# haasoscope_pro_input_board.net
KiCad netlist of a schematic drawn in EAGLE
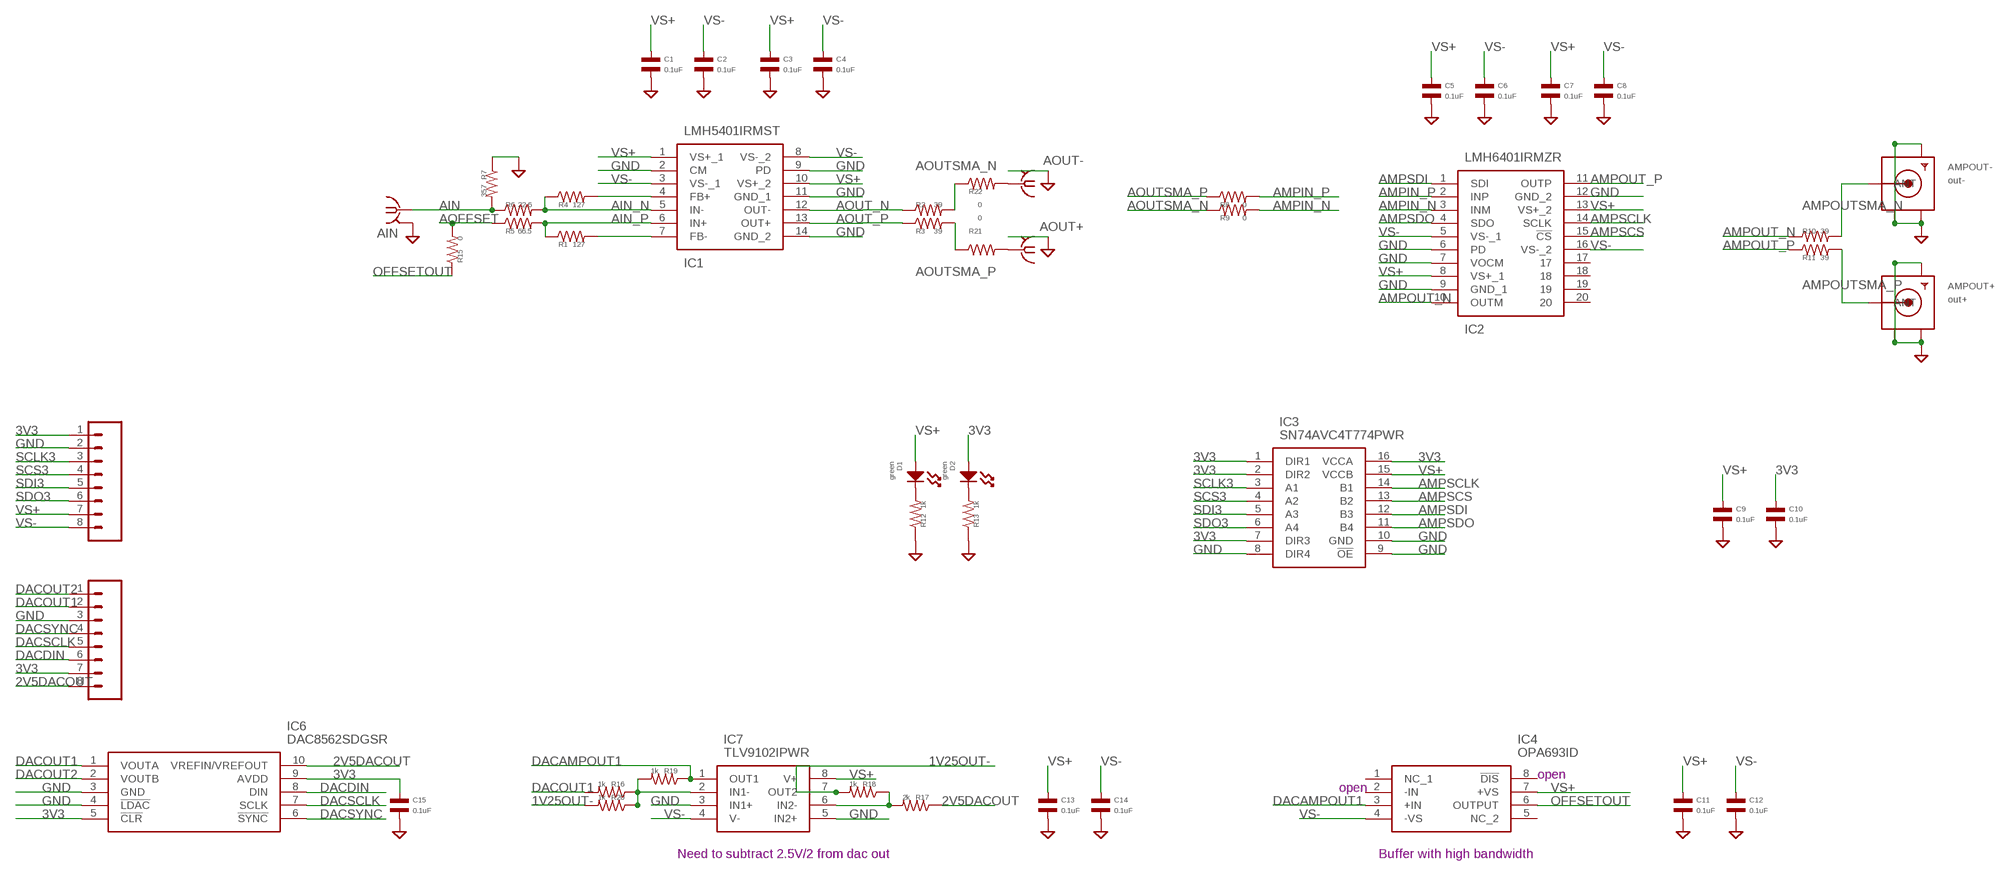
[diagram p0: schematic, sheet 1]

(export (version "E")
  (design (tool "Eeschema 10.0.6"))
  (components
    (comp (ref "AIN")
      (value "BU-SMB-V")
      (footprint "eagle-import:BU-SMB-V")
      (libsource (lib "eagle-import") (part "BU-SMB-V"))
    )
    (comp (ref "AMPOUT+")
      (value "out+")
      (footprint "eagle-import:SMA_EDGELAUNCH")
      (libsource (lib "eagle-import") (part "SMACONNECTOR_EDGE"))
    )
    (comp (ref "AMPOUT-")
      (value "out-")
      (footprint "eagle-import:SMA_EDGELAUNCH")
      (libsource (lib "eagle-import") (part "SMACONNECTOR_EDGE"))
    )
    (comp (ref "AOUT+")
      (value "BU-SMB-V")
      (footprint "eagle-import:BU-SMB-V")
      (libsource (lib "eagle-import") (part "BU-SMB-V"))
    )
    (comp (ref "AOUT-")
      (value "BU-SMB-V")
      (footprint "eagle-import:BU-SMB-V")
      (libsource (lib "eagle-import") (part "BU-SMB-V"))
    )
    (comp (ref "C1")
      (value "0.1uF")
      (footprint "eagle-import:C0402")
      (libsource (lib "eagle-import") (part "CAPACITOR_NP_0402"))
    )
    (comp (ref "C2")
      (value "0.1uF")
      (footprint "eagle-import:C0402")
      (libsource (lib "eagle-import") (part "CAPACITOR_NP_0402"))
    )
    (comp (ref "C3")
      (value "0.1uF")
      (footprint "eagle-import:C0402")
      (libsource (lib "eagle-import") (part "CAPACITOR_NP_0402"))
    )
    (comp (ref "C4")
      (value "0.1uF")
      (footprint "eagle-import:C0402")
      (libsource (lib "eagle-import") (part "CAPACITOR_NP_0402"))
    )
    (comp (ref "C5")
      (value "0.1uF")
      (footprint "eagle-import:C0402")
      (libsource (lib "eagle-import") (part "CAPACITOR_NP_0402"))
    )
    (comp (ref "C6")
      (value "0.1uF")
      (footprint "eagle-import:C0402")
      (libsource (lib "eagle-import") (part "CAPACITOR_NP_0402"))
    )
    (comp (ref "C7")
      (value "0.1uF")
      (footprint "eagle-import:C0402")
      (libsource (lib "eagle-import") (part "CAPACITOR_NP_0402"))
    )
    (comp (ref "C8")
      (value "0.1uF")
      (footprint "eagle-import:C0402")
      (libsource (lib "eagle-import") (part "CAPACITOR_NP_0402"))
    )
    (comp (ref "C9")
      (value "0.1uF")
      (footprint "eagle-import:C0402")
      (libsource (lib "eagle-import") (part "CAPACITOR_NP_0402"))
    )
    (comp (ref "C10")
      (value "0.1uF")
      (footprint "eagle-import:C0402")
      (libsource (lib "eagle-import") (part "CAPACITOR_NP_0402"))
    )
    (comp (ref "C11")
      (value "0.1uF")
      (footprint "eagle-import:C0402")
      (libsource (lib "eagle-import") (part "CAPACITOR_NP_0402"))
    )
    (comp (ref "C12")
      (value "0.1uF")
      (footprint "eagle-import:C0402")
      (libsource (lib "eagle-import") (part "CAPACITOR_NP_0402"))
    )
    (comp (ref "C13")
      (value "0.1uF")
      (footprint "eagle-import:C0402")
      (libsource (lib "eagle-import") (part "CAPACITOR_NP_0402"))
    )
    (comp (ref "C14")
      (value "0.1uF")
      (footprint "eagle-import:C0402")
      (libsource (lib "eagle-import") (part "CAPACITOR_NP_0402"))
    )
    (comp (ref "C15")
      (value "0.1uF")
      (footprint "eagle-import:C0402")
      (libsource (lib "eagle-import") (part "CAPACITOR_NP_0402"))
    )
    (comp (ref "D1")
      (value "green")
      (footprint "eagle-import:LED0603")
      (fields (field (name "HOUSEPART") "NO"))
      (libsource (lib "eagle-import") (part "LED_SINGLE-0603"))
    )
    (comp (ref "D2")
      (value "green")
      (footprint "eagle-import:LED0603")
      (fields (field (name "HOUSEPART") "NO"))
      (libsource (lib "eagle-import") (part "LED_SINGLE-0603"))
    )
    (comp (ref "IC1")
      (value "LMH5401IRMST")
      (footprint "eagle-import:LMH5401IRMSR")
      (fields (field (name "MOUSER_PART_NUMBER") "595-LMH5401IRMST"))
      (libsource (lib "eagle-import") (part "LMH5401IRMST"))
    )
    (comp (ref "IC2")
      (value "LMH6401IRMZR")
      (footprint "eagle-import:LMH6401IRMZR")
      (fields (field (name "MOUSER_PART_NUMBER") "595-LMH6401IRMZR"))
      (libsource (lib "eagle-import") (part "LMH6401IRMZR"))
    )
    (comp (ref "IC3")
      (value "SN74AVC4T774PWR")
      (footprint "eagle-import:SOP65P640X120-16N")
      (fields (field (name "MOUSER_PART_NUMBER") "595-SN74AVC4T774PWR"))
      (libsource (lib "eagle-import") (part "SN74AVC4T774PWR"))
    )
    (comp (ref "IC4")
      (value "OPA693ID")
      (footprint "eagle-import:SOIC127P600X175-8N")
      (fields (field (name "MOUSER_PART_NUMBER") "595-OPA693ID"))
      (libsource (lib "eagle-import") (part "OPA693ID"))
    )
    (comp (ref "IC6")
      (value "DAC8562SDGSR")
      (footprint "eagle-import:SOP50P490X110-10N")
      (fields (field (name "MOUSER_PART_NUMBER") "595-DAC8562SDGSR"))
      (libsource (lib "eagle-import") (part "DAC8562SDGSR"))
    )
    (comp (ref "IC7")
      (value "TLV9102IPWR")
      (footprint "eagle-import:SOP65P640X120-8N")
      (fields (field (name "MOUSER_PART_NUMBER") "595-TLV9102IPWR"))
      (libsource (lib "eagle-import") (part "TLV9102IPWR"))
    )
    (comp (ref "J1")
      (value "8pin")
      (footprint "eagle-import:1X08")
      (libsource (lib "eagle-import") (part "CONN_08{dblquote}"))
    )
    (comp (ref "J4")
      (value "8pin")
      (footprint "eagle-import:1X08")
      (libsource (lib "eagle-import") (part "CONN_08{dblquote}"))
    )
    (comp (ref "R1")
      (value "127")
      (footprint "eagle-import:R0402")
      (libsource (lib "eagle-import") (part "RESISTOR_0402"))
    )
    (comp (ref "R2")
      (value "39")
      (footprint "eagle-import:R0402")
      (libsource (lib "eagle-import") (part "RESISTOR_0402"))
    )
    (comp (ref "R3")
      (value "39")
      (footprint "eagle-import:R0402")
      (libsource (lib "eagle-import") (part "RESISTOR_0402"))
    )
    (comp (ref "R4")
      (value "127")
      (footprint "eagle-import:R0402")
      (libsource (lib "eagle-import") (part "RESISTOR_0402"))
    )
    (comp (ref "R5")
      (value "66.5")
      (footprint "eagle-import:R0402")
      (libsource (lib "eagle-import") (part "RESISTOR_0402"))
    )
    (comp (ref "R6")
      (value "22.6")
      (footprint "eagle-import:R0402")
      (libsource (lib "eagle-import") (part "RESISTOR_0402"))
    )
    (comp (ref "R7")
      (value "357")
      (footprint "eagle-import:R0402")
      (libsource (lib "eagle-import") (part "RESISTOR_0402"))
    )
    (comp (ref "R8")
      (value "0")
      (footprint "eagle-import:R0402")
      (libsource (lib "eagle-import") (part "RESISTOR_0402"))
    )
    (comp (ref "R9")
      (value "0")
      (footprint "eagle-import:R0402")
      (libsource (lib "eagle-import") (part "RESISTOR_0402"))
    )
    (comp (ref "R10")
      (value "39")
      (footprint "eagle-import:R0402")
      (libsource (lib "eagle-import") (part "RESISTOR_0402"))
    )
    (comp (ref "R11")
      (value "39")
      (footprint "eagle-import:R0402")
      (libsource (lib "eagle-import") (part "RESISTOR_0402"))
    )
    (comp (ref "R12")
      (value "1k")
      (footprint "eagle-import:R0402")
      (libsource (lib "eagle-import") (part "RESISTOR_0402"))
    )
    (comp (ref "R13")
      (value "1k")
      (footprint "eagle-import:R0402")
      (libsource (lib "eagle-import") (part "RESISTOR_0402"))
    )
    (comp (ref "R15")
      (value "0")
      (footprint "eagle-import:R0402")
      (libsource (lib "eagle-import") (part "RESISTOR_0402"))
    )
    (comp (ref "R16")
      (value "1k")
      (footprint "eagle-import:R0402")
      (libsource (lib "eagle-import") (part "RESISTOR_0402"))
    )
    (comp (ref "R17")
      (value "2k")
      (footprint "eagle-import:R0402")
      (libsource (lib "eagle-import") (part "RESISTOR_0402"))
    )
    (comp (ref "R18")
      (value "1k")
      (footprint "eagle-import:R0402")
      (libsource (lib "eagle-import") (part "RESISTOR_0402"))
    )
    (comp (ref "R19")
      (value "1k")
      (footprint "eagle-import:R0402")
      (libsource (lib "eagle-import") (part "RESISTOR_0402"))
    )
    (comp (ref "R20")
      (value "1k")
      (footprint "eagle-import:R0402")
      (libsource (lib "eagle-import") (part "RESISTOR_0402"))
    )
    (comp (ref "R21")
      (value "0")
      (footprint "eagle-import:R0402")
      (libsource (lib "eagle-import") (part "RESISTOR_0402"))
    )
    (comp (ref "R22")
      (value "0")
      (footprint "eagle-import:R0402")
      (libsource (lib "eagle-import") (part "RESISTOR_0402"))
    )
  )
  (nets
    (net (code "1") (name "/1V25OUT-") (class "Default")
      (node (ref "IC7") (pin "7") (pinfunction "OUT2_7") (pintype "bidirectional"))
      (node (ref "R18") (pin "P$2") (pinfunction "P$2_P$2") (pintype "passive"))
      (node (ref "R20") (pin "P$2") (pinfunction "P$2_P$2") (pintype "passive"))
    )
    (net (code "2") (name "/2V5DACOUT") (class "Default")
      (node (ref "IC6") (pin "10") (pinfunction "VREFIN/VREFOUT_10") (pintype "bidirectional"))
      (node (ref "J1") (pin "8") (pinfunction "8_8") (pintype "passive"))
      (node (ref "R17") (pin "P$1") (pinfunction "P$1_P$1") (pintype "passive"))
    )
    (net (code "3") (name "/3V3") (class "Default")
      (node (ref "C10") (pin "P$1") (pinfunction "P$1_P$1") (pintype "passive"))
      (node (ref "C15") (pin "P$1") (pinfunction "P$1_P$1") (pintype "passive"))
      (node (ref "D2") (pin "ANODE") (pinfunction "ANODE_ANODE") (pintype "power_in"))
      (node (ref "IC3") (pin "1") (pinfunction "DIR1_1") (pintype "bidirectional"))
      (node (ref "IC3") (pin "16") (pinfunction "VCCA_16") (pintype "bidirectional"))
      (node (ref "IC3") (pin "2") (pinfunction "DIR2_2") (pintype "bidirectional"))
      (node (ref "IC3") (pin "7") (pinfunction "DIR3_7") (pintype "bidirectional"))
      (node (ref "IC6") (pin "5") (pinfunction "~{CLR}_5") (pintype "bidirectional"))
      (node (ref "IC6") (pin "9") (pinfunction "AVDD_9") (pintype "bidirectional"))
      (node (ref "J1") (pin "7") (pinfunction "7_7") (pintype "passive"))
      (node (ref "J4") (pin "1") (pinfunction "1_1") (pintype "passive"))
    )
    (net (code "4") (name "/AIN") (class "Default")
      (node (ref "AIN") (pin "1") (pinfunction "1_1") (pintype "passive"))
      (node (ref "R6") (pin "P$1") (pinfunction "P$1_P$1") (pintype "passive"))
      (node (ref "R7") (pin "P$2") (pinfunction "P$2_P$2") (pintype "passive"))
    )
    (net (code "5") (name "/AIN_N") (class "Default")
      (node (ref "IC1") (pin "5") (pinfunction "IN-_5") (pintype "bidirectional"))
      (node (ref "R4") (pin "P$1") (pinfunction "P$1_P$1") (pintype "passive"))
      (node (ref "R6") (pin "P$2") (pinfunction "P$2_P$2") (pintype "passive"))
    )
    (net (code "6") (name "/AIN_P") (class "Default")
      (node (ref "IC1") (pin "6") (pinfunction "IN+_6") (pintype "bidirectional"))
      (node (ref "R1") (pin "P$1") (pinfunction "P$1_P$1") (pintype "passive"))
      (node (ref "R5") (pin "P$2") (pinfunction "P$2_P$2") (pintype "passive"))
    )
    (net (code "7") (name "/AMPIN_N") (class "Default")
      (node (ref "IC2") (pin "3") (pinfunction "INM_3") (pintype "bidirectional"))
      (node (ref "R9") (pin "P$2") (pinfunction "P$2_P$2") (pintype "passive"))
    )
    (net (code "8") (name "/AMPIN_P") (class "Default")
      (node (ref "IC2") (pin "2") (pinfunction "INP_2") (pintype "bidirectional"))
      (node (ref "R8") (pin "P$2") (pinfunction "P$2_P$2") (pintype "passive"))
    )
    (net (code "9") (name "/AMPOUTSMA_N") (class "Default")
      (node (ref "AMPOUT-") (pin "P") (pinfunction "ANT_P") (pintype "bidirectional"))
      (node (ref "R10") (pin "P$2") (pinfunction "P$2_P$2") (pintype "passive"))
    )
    (net (code "10") (name "/AMPOUTSMA_P") (class "Default")
      (node (ref "AMPOUT+") (pin "P") (pinfunction "ANT_P") (pintype "bidirectional"))
      (node (ref "R11") (pin "P$2") (pinfunction "P$2_P$2") (pintype "passive"))
    )
    (net (code "11") (name "/AMPOUT_N") (class "Default")
      (node (ref "IC2") (pin "10") (pinfunction "OUTM_10") (pintype "bidirectional"))
      (node (ref "R10") (pin "P$1") (pinfunction "P$1_P$1") (pintype "passive"))
    )
    (net (code "12") (name "/AMPOUT_P") (class "Default")
      (node (ref "IC2") (pin "11") (pinfunction "OUTP_11") (pintype "bidirectional"))
      (node (ref "R11") (pin "P$1") (pinfunction "P$1_P$1") (pintype "passive"))
    )
    (net (code "13") (name "/AMPSCLK") (class "Default")
      (node (ref "IC2") (pin "14") (pinfunction "SCLK_14") (pintype "bidirectional"))
      (node (ref "IC3") (pin "14") (pinfunction "B1_14") (pintype "bidirectional"))
    )
    (net (code "14") (name "/AMPSCS") (class "Default")
      (node (ref "IC2") (pin "15") (pinfunction "~{CS}_15") (pintype "bidirectional"))
      (node (ref "IC3") (pin "13") (pinfunction "B2_13") (pintype "bidirectional"))
    )
    (net (code "15") (name "/AMPSDI") (class "Default")
      (node (ref "IC2") (pin "1") (pinfunction "SDI_1") (pintype "bidirectional"))
      (node (ref "IC3") (pin "12") (pinfunction "B3_12") (pintype "bidirectional"))
    )
    (net (code "16") (name "/AMPSDO") (class "Default")
      (node (ref "IC2") (pin "4") (pinfunction "SDO_4") (pintype "bidirectional"))
      (node (ref "IC3") (pin "11") (pinfunction "B4_11") (pintype "bidirectional"))
    )
    (net (code "17") (name "/AOFFSET") (class "Default")
      (node (ref "R15") (pin "P$2") (pinfunction "P$2_P$2") (pintype "passive"))
      (node (ref "R5") (pin "P$1") (pinfunction "P$1_P$1") (pintype "passive"))
    )
    (net (code "18") (name "/AOUTSMA_N") (class "Default")
      (node (ref "R2") (pin "P$2") (pinfunction "P$2_P$2") (pintype "passive"))
      (node (ref "R22") (pin "P$1") (pinfunction "P$1_P$1") (pintype "passive"))
      (node (ref "R9") (pin "P$1") (pinfunction "P$1_P$1") (pintype "passive"))
    )
    (net (code "19") (name "/AOUTSMA_P") (class "Default")
      (node (ref "R21") (pin "P$1") (pinfunction "P$1_P$1") (pintype "passive"))
      (node (ref "R3") (pin "P$2") (pinfunction "P$2_P$2") (pintype "passive"))
      (node (ref "R8") (pin "P$1") (pinfunction "P$1_P$1") (pintype "passive"))
    )
    (net (code "20") (name "/AOUT_N") (class "Default")
      (node (ref "IC1") (pin "12") (pinfunction "OUT-_12") (pintype "bidirectional"))
      (node (ref "R2") (pin "P$1") (pinfunction "P$1_P$1") (pintype "passive"))
    )
    (net (code "21") (name "/AOUT_P") (class "Default")
      (node (ref "IC1") (pin "13") (pinfunction "OUT+_13") (pintype "bidirectional"))
      (node (ref "R3") (pin "P$1") (pinfunction "P$1_P$1") (pintype "passive"))
    )
    (net (code "22") (name "/DACAMPOUT1") (class "Default")
      (node (ref "IC4") (pin "3") (pinfunction "+IN_3") (pintype "bidirectional"))
      (node (ref "IC7") (pin "1") (pinfunction "OUT1_1") (pintype "bidirectional"))
      (node (ref "R19") (pin "P$1") (pinfunction "P$1_P$1") (pintype "passive"))
    )
    (net (code "23") (name "/DACDIN") (class "Default")
      (node (ref "IC6") (pin "8") (pinfunction "DIN_8") (pintype "bidirectional"))
      (node (ref "J1") (pin "6") (pinfunction "6_6") (pintype "passive"))
    )
    (net (code "24") (name "/DACOUT1") (class "Default")
      (node (ref "IC6") (pin "1") (pinfunction "VOUTA_1") (pintype "bidirectional"))
      (node (ref "J1") (pin "2") (pinfunction "2_2") (pintype "passive"))
      (node (ref "R16") (pin "P$2") (pinfunction "P$2_P$2") (pintype "passive"))
    )
    (net (code "25") (name "/DACOUT2") (class "Default")
      (node (ref "IC6") (pin "2") (pinfunction "VOUTB_2") (pintype "bidirectional"))
      (node (ref "J1") (pin "1") (pinfunction "1_1") (pintype "passive"))
    )
    (net (code "26") (name "/DACSCLK") (class "Default")
      (node (ref "IC6") (pin "7") (pinfunction "SCLK_7") (pintype "bidirectional"))
      (node (ref "J1") (pin "5") (pinfunction "5_5") (pintype "passive"))
    )
    (net (code "27") (name "/DACSYNC") (class "Default")
      (node (ref "IC6") (pin "6") (pinfunction "~{SYNC}_6") (pintype "bidirectional"))
      (node (ref "J1") (pin "4") (pinfunction "4_4") (pintype "passive"))
    )
    (net (code "28") (name "/OFFSETOUT") (class "Default")
      (node (ref "IC4") (pin "6") (pinfunction "OUTPUT_6") (pintype "bidirectional"))
      (node (ref "R15") (pin "P$1") (pinfunction "P$1_P$1") (pintype "passive"))
    )
    (net (code "29") (name "/SCLK3") (class "Default")
      (node (ref "IC3") (pin "3") (pinfunction "A1_3") (pintype "bidirectional"))
      (node (ref "J4") (pin "3") (pinfunction "3_3") (pintype "passive"))
    )
    (net (code "30") (name "/SCS3") (class "Default")
      (node (ref "IC3") (pin "4") (pinfunction "A2_4") (pintype "bidirectional"))
      (node (ref "J4") (pin "4") (pinfunction "4_4") (pintype "passive"))
    )
    (net (code "31") (name "/SDI3") (class "Default")
      (node (ref "IC3") (pin "5") (pinfunction "A3_5") (pintype "bidirectional"))
      (node (ref "J4") (pin "5") (pinfunction "5_5") (pintype "passive"))
    )
    (net (code "32") (name "/SDO3") (class "Default")
      (node (ref "IC3") (pin "6") (pinfunction "A4_6") (pintype "bidirectional"))
      (node (ref "J4") (pin "6") (pinfunction "6_6") (pintype "passive"))
    )
    (net (code "33") (name "/VS+") (class "Default")
      (node (ref "C1") (pin "P$1") (pinfunction "P$1_P$1") (pintype "passive"))
      (node (ref "C11") (pin "P$1") (pinfunction "P$1_P$1") (pintype "passive"))
      (node (ref "C13") (pin "P$1") (pinfunction "P$1_P$1") (pintype "passive"))
      (node (ref "C3") (pin "P$1") (pinfunction "P$1_P$1") (pintype "passive"))
      (node (ref "C5") (pin "P$1") (pinfunction "P$1_P$1") (pintype "passive"))
      (node (ref "C7") (pin "P$1") (pinfunction "P$1_P$1") (pintype "passive"))
      (node (ref "C9") (pin "P$1") (pinfunction "P$1_P$1") (pintype "passive"))
      (node (ref "D1") (pin "ANODE") (pinfunction "ANODE_ANODE") (pintype "power_in"))
      (node (ref "IC1") (pin "1") (pinfunction "VS+_1_1") (pintype "bidirectional"))
      (node (ref "IC1") (pin "10") (pinfunction "VS+_2_10") (pintype "bidirectional"))
      (node (ref "IC2") (pin "13") (pinfunction "VS+_2_13") (pintype "bidirectional"))
      (node (ref "IC2") (pin "8") (pinfunction "VS+_1_8") (pintype "bidirectional"))
      (node (ref "IC3") (pin "15") (pinfunction "VCCB_15") (pintype "bidirectional"))
      (node (ref "IC4") (pin "7") (pinfunction "+VS_7") (pintype "bidirectional"))
      (node (ref "IC7") (pin "8") (pinfunction "V+_8") (pintype "bidirectional"))
      (node (ref "J4") (pin "7") (pinfunction "7_7") (pintype "passive"))
    )
    (net (code "34") (name "/VS-") (class "Default")
      (node (ref "C12") (pin "P$1") (pinfunction "P$1_P$1") (pintype "passive"))
      (node (ref "C14") (pin "P$1") (pinfunction "P$1_P$1") (pintype "passive"))
      (node (ref "C2") (pin "P$1") (pinfunction "P$1_P$1") (pintype "passive"))
      (node (ref "C4") (pin "P$1") (pinfunction "P$1_P$1") (pintype "passive"))
      (node (ref "C6") (pin "P$1") (pinfunction "P$1_P$1") (pintype "passive"))
      (node (ref "C8") (pin "P$1") (pinfunction "P$1_P$1") (pintype "passive"))
      (node (ref "IC1") (pin "3") (pinfunction "VS-_1_3") (pintype "bidirectional"))
      (node (ref "IC1") (pin "8") (pinfunction "VS-_2_8") (pintype "bidirectional"))
      (node (ref "IC2") (pin "16") (pinfunction "VS-_2_16") (pintype "bidirectional"))
      (node (ref "IC2") (pin "5") (pinfunction "VS-_1_5") (pintype "bidirectional"))
      (node (ref "IC4") (pin "4") (pinfunction "-VS_4") (pintype "bidirectional"))
      (node (ref "IC7") (pin "4") (pinfunction "V-_4") (pintype "bidirectional"))
      (node (ref "J4") (pin "8") (pinfunction "8_8") (pintype "passive"))
    )
    (net (code "35") (name "GND") (class "Default")
      (node (ref "AIN") (pin "2") (pinfunction "2_2") (pintype "passive"))
      (node (ref "AIN") (pin "3") (pinfunction "2_3") (pintype "passive"))
      (node (ref "AIN") (pin "4") (pinfunction "2_4") (pintype "passive"))
      (node (ref "AIN") (pin "5") (pinfunction "2_5") (pintype "passive"))
      (node (ref "AMPOUT+") (pin "GND@1") (pinfunction "GND4_GND@1") (pintype "power_in"))
      (node (ref "AMPOUT+") (pin "GND@2") (pinfunction "GND3_GND@2") (pintype "power_in"))
      (node (ref "AMPOUT+") (pin "GND@3") (pinfunction "GND2_GND@3") (pintype "power_in"))
      (node (ref "AMPOUT+") (pin "GND@4") (pinfunction "GND1_GND@4") (pintype "power_in"))
      (node (ref "AMPOUT-") (pin "GND@1") (pinfunction "GND4_GND@1") (pintype "power_in"))
      (node (ref "AMPOUT-") (pin "GND@2") (pinfunction "GND3_GND@2") (pintype "power_in"))
      (node (ref "AMPOUT-") (pin "GND@3") (pinfunction "GND2_GND@3") (pintype "power_in"))
      (node (ref "AMPOUT-") (pin "GND@4") (pinfunction "GND1_GND@4") (pintype "power_in"))
      (node (ref "AOUT+") (pin "2") (pinfunction "2_2") (pintype "passive"))
      (node (ref "AOUT+") (pin "3") (pinfunction "2_3") (pintype "passive"))
      (node (ref "AOUT+") (pin "4") (pinfunction "2_4") (pintype "passive"))
      (node (ref "AOUT+") (pin "5") (pinfunction "2_5") (pintype "passive"))
      (node (ref "AOUT-") (pin "2") (pinfunction "2_2") (pintype "passive"))
      (node (ref "AOUT-") (pin "3") (pinfunction "2_3") (pintype "passive"))
      (node (ref "AOUT-") (pin "4") (pinfunction "2_4") (pintype "passive"))
      (node (ref "AOUT-") (pin "5") (pinfunction "2_5") (pintype "passive"))
      (node (ref "C1") (pin "P$2") (pinfunction "P$2_P$2") (pintype "passive"))
      (node (ref "C10") (pin "P$2") (pinfunction "P$2_P$2") (pintype "passive"))
      (node (ref "C11") (pin "P$2") (pinfunction "P$2_P$2") (pintype "passive"))
      (node (ref "C12") (pin "P$2") (pinfunction "P$2_P$2") (pintype "passive"))
      (node (ref "C13") (pin "P$2") (pinfunction "P$2_P$2") (pintype "passive"))
      (node (ref "C14") (pin "P$2") (pinfunction "P$2_P$2") (pintype "passive"))
      (node (ref "C15") (pin "P$2") (pinfunction "P$2_P$2") (pintype "passive"))
      (node (ref "C2") (pin "P$2") (pinfunction "P$2_P$2") (pintype "passive"))
      (node (ref "C3") (pin "P$2") (pinfunction "P$2_P$2") (pintype "passive"))
      (node (ref "C4") (pin "P$2") (pinfunction "P$2_P$2") (pintype "passive"))
      (node (ref "C5") (pin "P$2") (pinfunction "P$2_P$2") (pintype "passive"))
      (node (ref "C6") (pin "P$2") (pinfunction "P$2_P$2") (pintype "passive"))
      (node (ref "C7") (pin "P$2") (pinfunction "P$2_P$2") (pintype "passive"))
      (node (ref "C8") (pin "P$2") (pinfunction "P$2_P$2") (pintype "passive"))
      (node (ref "C9") (pin "P$2") (pinfunction "P$2_P$2") (pintype "passive"))
      (node (ref "IC1") (pin "11") (pinfunction "GND_1_11") (pintype "bidirectional"))
      (node (ref "IC1") (pin "14") (pinfunction "GND_2_14") (pintype "bidirectional"))
      (node (ref "IC1") (pin "2") (pinfunction "CM_2") (pintype "bidirectional"))
      (node (ref "IC1") (pin "9") (pinfunction "PD_9") (pintype "bidirectional"))
      (node (ref "IC2") (pin "12") (pinfunction "GND_2_12") (pintype "bidirectional"))
      (node (ref "IC2") (pin "6") (pinfunction "PD_6") (pintype "bidirectional"))
      (node (ref "IC2") (pin "7") (pinfunction "VOCM_7") (pintype "bidirectional"))
      (node (ref "IC2") (pin "9") (pinfunction "GND_1_9") (pintype "bidirectional"))
      (node (ref "IC3") (pin "10") (pinfunction "GND_10") (pintype "bidirectional"))
      (node (ref "IC3") (pin "8") (pinfunction "DIR4_8") (pintype "bidirectional"))
      (node (ref "IC3") (pin "9") (pinfunction "~{OE}_9") (pintype "bidirectional"))
      (node (ref "IC6") (pin "3") (pinfunction "GND_3") (pintype "bidirectional"))
      (node (ref "IC6") (pin "4") (pinfunction "~{LDAC}_4") (pintype "bidirectional"))
      (node (ref "IC7") (pin "3") (pinfunction "IN1+_3") (pintype "bidirectional"))
      (node (ref "IC7") (pin "5") (pinfunction "IN2+_5") (pintype "bidirectional"))
      (node (ref "J1") (pin "3") (pinfunction "3_3") (pintype "passive"))
      (node (ref "J4") (pin "2") (pinfunction "2_2") (pintype "passive"))
      (node (ref "R12") (pin "P$1") (pinfunction "P$1_P$1") (pintype "passive"))
      (node (ref "R13") (pin "P$1") (pinfunction "P$1_P$1") (pintype "passive"))
      (node (ref "R7") (pin "P$1") (pinfunction "P$1_P$1") (pintype "passive"))
    )
    (net (code "36") (name "Net-(AOUT+-Pad1)") (class "Default")
      (node (ref "AOUT+") (pin "1") (pinfunction "1_1") (pintype "passive"))
      (node (ref "R21") (pin "P$2") (pinfunction "P$2_P$2") (pintype "passive"))
    )
    (net (code "37") (name "Net-(AOUT--Pad1)") (class "Default")
      (node (ref "AOUT-") (pin "1") (pinfunction "1_1") (pintype "passive"))
      (node (ref "R22") (pin "P$2") (pinfunction "P$2_P$2") (pintype "passive"))
    )
    (net (code "38") (name "Net-(D1-PadCATHODE)") (class "Default")
      (node (ref "D1") (pin "CATHODE") (pinfunction "CATHODE_CATHODE") (pintype "power_in"))
      (node (ref "R12") (pin "P$2") (pinfunction "P$2_P$2") (pintype "passive"))
    )
    (net (code "39") (name "Net-(D2-PadCATHODE)") (class "Default")
      (node (ref "D2") (pin "CATHODE") (pinfunction "CATHODE_CATHODE") (pintype "power_in"))
      (node (ref "R13") (pin "P$2") (pinfunction "P$2_P$2") (pintype "passive"))
    )
    (net (code "40") (name "Net-(IC1-FB+)") (class "Default")
      (node (ref "IC1") (pin "4") (pinfunction "FB+_4") (pintype "bidirectional"))
      (node (ref "R4") (pin "P$2") (pinfunction "P$2_P$2") (pintype "passive"))
    )
    (net (code "41") (name "Net-(IC1-FB-)") (class "Default")
      (node (ref "IC1") (pin "7") (pinfunction "FB-_7") (pintype "bidirectional"))
      (node (ref "R1") (pin "P$2") (pinfunction "P$2_P$2") (pintype "passive"))
    )
    (net (code "42") (name "Net-(IC7-IN1-)") (class "Default")
      (node (ref "IC7") (pin "2") (pinfunction "IN1-_2") (pintype "bidirectional"))
      (node (ref "R16") (pin "P$1") (pinfunction "P$1_P$1") (pintype "passive"))
      (node (ref "R19") (pin "P$2") (pinfunction "P$2_P$2") (pintype "passive"))
      (node (ref "R20") (pin "P$1") (pinfunction "P$1_P$1") (pintype "passive"))
    )
    (net (code "43") (name "Net-(IC7-IN2-)") (class "Default")
      (node (ref "IC7") (pin "6") (pinfunction "IN2-_6") (pintype "bidirectional"))
      (node (ref "R17") (pin "P$2") (pinfunction "P$2_P$2") (pintype "passive"))
      (node (ref "R18") (pin "P$1") (pinfunction "P$1_P$1") (pintype "passive"))
    )
    (net (code "44") (name "unconnected-(IC2-Pad17)") (class "Default")
      (node (ref "IC2") (pin "17") (pinfunction "17_17") (pintype "bidirectional"))
    )
    (net (code "45") (name "unconnected-(IC2-Pad18)") (class "Default")
      (node (ref "IC2") (pin "18") (pinfunction "18_18") (pintype "bidirectional"))
    )
    (net (code "46") (name "unconnected-(IC2-Pad19)") (class "Default")
      (node (ref "IC2") (pin "19") (pinfunction "19_19") (pintype "bidirectional"))
    )
    (net (code "47") (name "unconnected-(IC2-Pad20)") (class "Default")
      (node (ref "IC2") (pin "20") (pinfunction "20_20") (pintype "bidirectional"))
    )
    (net (code "48") (name "unconnected-(IC4--IN-Pad2)") (class "Default")
      (node (ref "IC4") (pin "2") (pinfunction "-IN_2") (pintype "bidirectional"))
    )
    (net (code "49") (name "unconnected-(IC4-NC_1-Pad1)") (class "Default")
      (node (ref "IC4") (pin "1") (pinfunction "NC_1_1") (pintype "bidirectional"))
    )
    (net (code "50") (name "unconnected-(IC4-NC_2-Pad5)") (class "Default")
      (node (ref "IC4") (pin "5") (pinfunction "NC_2_5") (pintype "bidirectional"))
    )
    (net (code "51") (name "unconnected-(IC4-~{DIS}-Pad8)") (class "Default")
      (node (ref "IC4") (pin "8") (pinfunction "~{DIS}_8") (pintype "bidirectional"))
    )
  )
)
